# DAQ_IO.net
KiCad netlist of a schematic drawn in Altium Designer
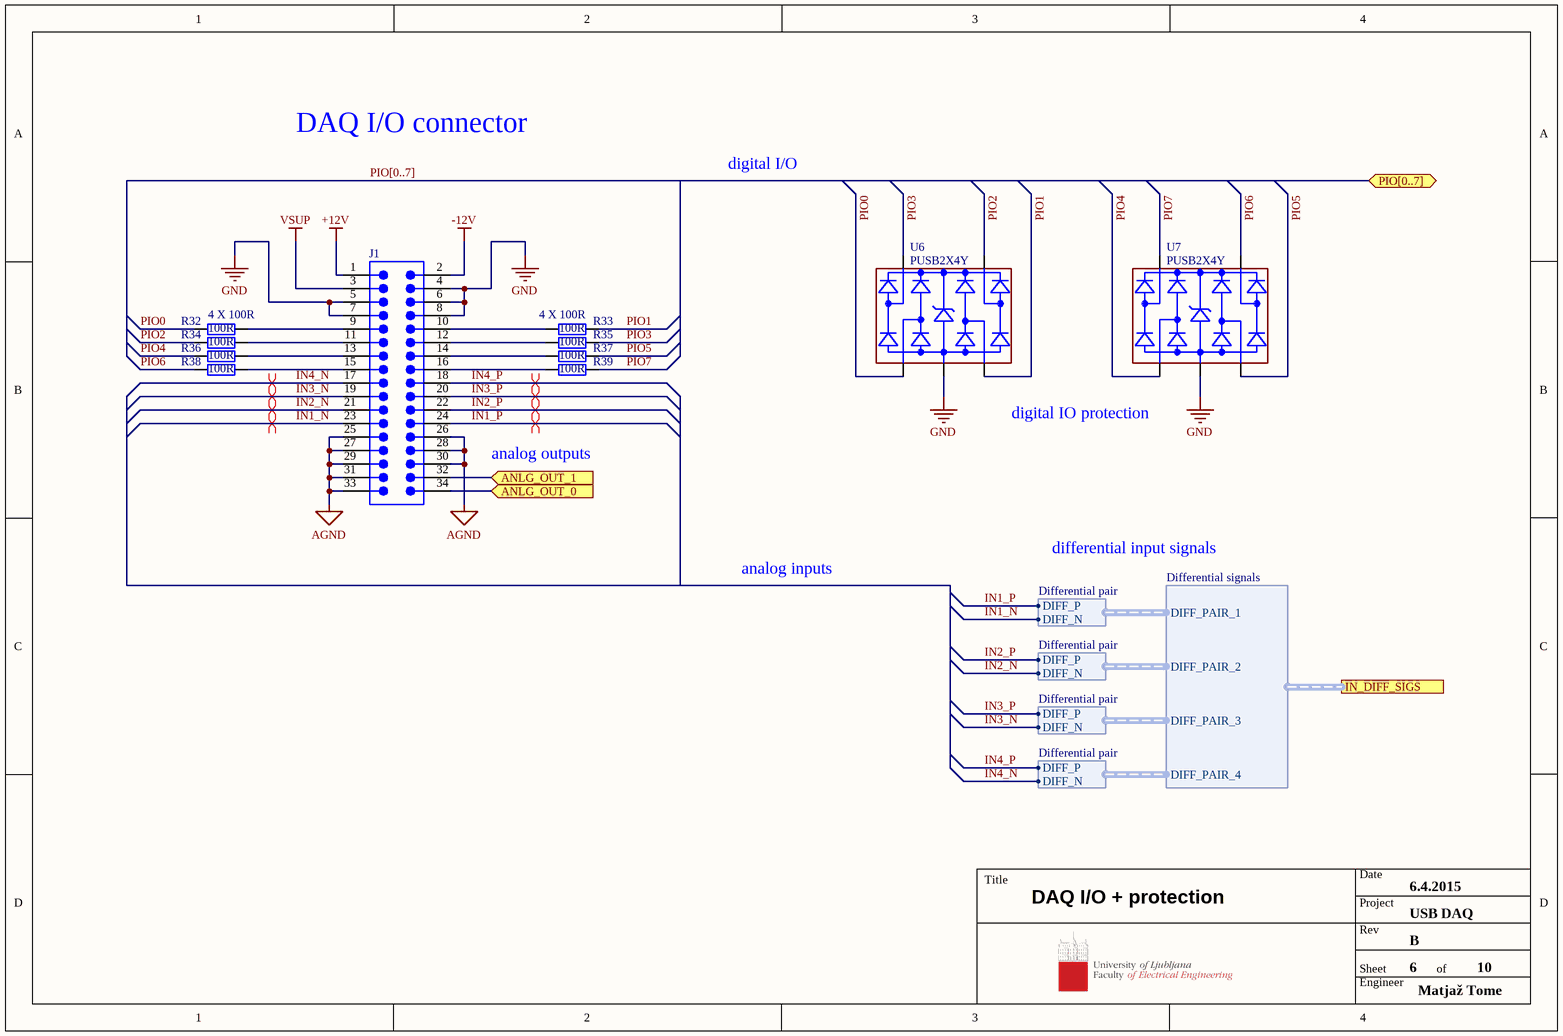
[diagram p0: DAQ_IO.SchDoc]

(export (version "E")
  (design (tool "Eeschema 10.0.6"))
  (components
    (comp (ref "J1")
      (value "2X17")
      (footprint "IDC34R")
      (description "Pin Header, Right Angle, Wire-to-Board, 2.54 mm, 2 Rows, 34 Contacts, Through Hole Right Angle")
      (fields (field (name "MANUFACTURER") "Harting"))
      (libsource (lib "DAQ") (part "09 18 534 7323"))
    )
    (comp (ref "R32")
      (value "100R")
      (footprint "R_0603")
      (description "Generic resistor")
      (fields (field (name "Comment") "comment"))
      (libsource (lib "DAQ") (part "Resistor"))
    )
    (comp (ref "R33")
      (value "100R")
      (footprint "R_0603")
      (description "Generic resistor")
      (fields (field (name "Comment") "comment"))
      (libsource (lib "DAQ") (part "Resistor"))
    )
    (comp (ref "R34")
      (value "100R")
      (footprint "R_0603")
      (description "Generic resistor")
      (fields (field (name "Comment") "comment"))
      (libsource (lib "DAQ") (part "Resistor"))
    )
    (comp (ref "R35")
      (value "100R")
      (footprint "R_0603")
      (description "Generic resistor")
      (fields (field (name "Comment") "comment"))
      (libsource (lib "DAQ") (part "Resistor"))
    )
    (comp (ref "R36")
      (value "100R")
      (footprint "R_0603")
      (description "Generic resistor")
      (fields (field (name "Comment") "comment"))
      (libsource (lib "DAQ") (part "Resistor"))
    )
    (comp (ref "R37")
      (value "100R")
      (footprint "R_0603")
      (description "Generic resistor")
      (fields (field (name "Comment") "comment"))
      (libsource (lib "DAQ") (part "Resistor"))
    )
    (comp (ref "R38")
      (value "100R")
      (footprint "R_0603")
      (description "Generic resistor")
      (fields (field (name "Comment") "comment"))
      (libsource (lib "DAQ") (part "Resistor"))
    )
    (comp (ref "R39")
      (value "100R")
      (footprint "R_0603")
      (description "Generic resistor")
      (fields (field (name "Comment") "comment"))
      (libsource (lib "DAQ") (part "Resistor"))
    )
    (comp (ref "U6")
      (value "PUSB2X4Y")
      (footprint "SOT363")
      (description "ESD protection for high-speed interfaces")
      (fields (field (name "PART NUMBER") "XDE0000") (field (name "MANUFACTURER") "Multicomp"))
      (libsource (lib "DAQ") (part "PUSB2X4Y"))
    )
    (comp (ref "U7")
      (value "PUSB2X4Y")
      (footprint "SOT363")
      (description "ESD protection for high-speed interfaces")
      (fields (field (name "PART NUMBER") "XDE0000") (field (name "MANUFACTURER") "Multicomp"))
      (libsource (lib "DAQ") (part "PUSB2X4Y"))
    )
  )
  (nets
    (net (code "4") (name "+12V") (class "Default")
      (node (ref "J1") (pin "1") (pinfunction "1_1") (pintype "passive"))
    )
    (net (code "5") (name "-12V") (class "Default")
      (node (ref "J1") (pin "2") (pinfunction "2_2") (pintype "passive"))
    )
    (net (code "6") (name "/ANLG_OUT_0") (class "Default")
      (node (ref "J1") (pin "34") (pinfunction "34_34") (pintype "passive"))
    )
    (net (code "7") (name "/ANLG_OUT_1") (class "Default")
      (node (ref "J1") (pin "32") (pinfunction "32_32") (pintype "passive"))
    )
    (net (code "8") (name "/IN1_N") (class "Default")
      (node (ref "J1") (pin "23") (pinfunction "23_23") (pintype "passive"))
    )
    (net (code "9") (name "/IN1_P") (class "Default")
      (node (ref "J1") (pin "24") (pinfunction "24_24") (pintype "passive"))
    )
    (net (code "10") (name "/IN2_N") (class "Default")
      (node (ref "J1") (pin "21") (pinfunction "21_21") (pintype "passive"))
    )
    (net (code "11") (name "/IN2_P") (class "Default")
      (node (ref "J1") (pin "22") (pinfunction "22_22") (pintype "passive"))
    )
    (net (code "12") (name "/IN3_N") (class "Default")
      (node (ref "J1") (pin "19") (pinfunction "19_19") (pintype "passive"))
    )
    (net (code "13") (name "/IN3_P") (class "Default")
      (node (ref "J1") (pin "20") (pinfunction "20_20") (pintype "passive"))
    )
    (net (code "14") (name "/IN4_N") (class "Default")
      (node (ref "J1") (pin "17") (pinfunction "17_17") (pintype "passive"))
    )
    (net (code "15") (name "/IN4_P") (class "Default")
      (node (ref "J1") (pin "18") (pinfunction "18_18") (pintype "passive"))
    )
    (net (code "16") (name "/PIO0") (class "Default")
      (node (ref "R32") (pin "1") (pintype "passive"))
      (node (ref "U6") (pin "1") (pinfunction "1_1") (pintype "passive"))
    )
    (net (code "17") (name "/PIO1") (class "Default")
      (node (ref "R33") (pin "2") (pintype "passive"))
      (node (ref "U6") (pin "3") (pinfunction "3_3") (pintype "passive"))
    )
    (net (code "18") (name "/PIO2") (class "Default")
      (node (ref "R34") (pin "1") (pintype "passive"))
      (node (ref "U6") (pin "4") (pinfunction "4_4") (pintype "passive"))
    )
    (net (code "19") (name "/PIO3") (class "Default")
      (node (ref "R35") (pin "2") (pintype "passive"))
      (node (ref "U6") (pin "6") (pinfunction "6_6") (pintype "passive"))
    )
    (net (code "20") (name "/PIO4") (class "Default")
      (node (ref "R36") (pin "1") (pintype "passive"))
      (node (ref "U7") (pin "1") (pinfunction "1_1") (pintype "passive"))
    )
    (net (code "21") (name "/PIO5") (class "Default")
      (node (ref "R37") (pin "2") (pintype "passive"))
      (node (ref "U7") (pin "3") (pinfunction "3_3") (pintype "passive"))
    )
    (net (code "22") (name "/PIO6") (class "Default")
      (node (ref "R38") (pin "1") (pintype "passive"))
      (node (ref "U7") (pin "4") (pinfunction "4_4") (pintype "passive"))
    )
    (net (code "23") (name "/PIO7") (class "Default")
      (node (ref "R39") (pin "2") (pintype "passive"))
      (node (ref "U7") (pin "6") (pinfunction "6_6") (pintype "passive"))
    )
    (net (code "27") (name "AGND") (class "Default")
      (node (ref "J1") (pin "25") (pinfunction "25_25") (pintype "passive"))
      (node (ref "J1") (pin "26") (pinfunction "26_26") (pintype "passive"))
      (node (ref "J1") (pin "27") (pinfunction "27_27") (pintype "passive"))
      (node (ref "J1") (pin "28") (pinfunction "28_28") (pintype "passive"))
      (node (ref "J1") (pin "29") (pinfunction "29_29") (pintype "passive"))
      (node (ref "J1") (pin "30") (pinfunction "30_30") (pintype "passive"))
      (node (ref "J1") (pin "31") (pinfunction "31_31") (pintype "passive"))
      (node (ref "J1") (pin "33") (pinfunction "33_33") (pintype "passive"))
    )
    (net (code "28") (name "GND") (class "Default")
      (node (ref "J1") (pin "4") (pinfunction "4_4") (pintype "passive"))
      (node (ref "J1") (pin "5") (pinfunction "5_5") (pintype "passive"))
      (node (ref "J1") (pin "6") (pinfunction "6_6") (pintype "passive"))
      (node (ref "J1") (pin "7") (pinfunction "7_7") (pintype "passive"))
      (node (ref "J1") (pin "8") (pinfunction "8_8") (pintype "passive"))
      (node (ref "U6") (pin "2") (pinfunction "2_2") (pintype "passive"))
      (node (ref "U7") (pin "2") (pinfunction "2_2") (pintype "passive"))
    )
    (net (code "29") (name "Net-(J1-Pad9)") (class "Default")
      (node (ref "J1") (pin "9") (pinfunction "9_9") (pintype "passive"))
      (node (ref "R32") (pin "2") (pintype "passive"))
    )
    (net (code "30") (name "Net-(J1-Pad10)") (class "Default")
      (node (ref "J1") (pin "10") (pinfunction "10_10") (pintype "passive"))
      (node (ref "R33") (pin "1") (pintype "passive"))
    )
    (net (code "31") (name "Net-(J1-Pad11)") (class "Default")
      (node (ref "J1") (pin "11") (pinfunction "11_11") (pintype "passive"))
      (node (ref "R34") (pin "2") (pintype "passive"))
    )
    (net (code "32") (name "Net-(J1-Pad12)") (class "Default")
      (node (ref "J1") (pin "12") (pinfunction "12_12") (pintype "passive"))
      (node (ref "R35") (pin "1") (pintype "passive"))
    )
    (net (code "33") (name "Net-(J1-Pad13)") (class "Default")
      (node (ref "J1") (pin "13") (pinfunction "13_13") (pintype "passive"))
      (node (ref "R36") (pin "2") (pintype "passive"))
    )
    (net (code "34") (name "Net-(J1-Pad14)") (class "Default")
      (node (ref "J1") (pin "14") (pinfunction "14_14") (pintype "passive"))
      (node (ref "R37") (pin "1") (pintype "passive"))
    )
    (net (code "35") (name "Net-(J1-Pad15)") (class "Default")
      (node (ref "J1") (pin "15") (pinfunction "15_15") (pintype "passive"))
      (node (ref "R38") (pin "2") (pintype "passive"))
    )
    (net (code "36") (name "Net-(J1-Pad16)") (class "Default")
      (node (ref "J1") (pin "16") (pinfunction "16_16") (pintype "passive"))
      (node (ref "R39") (pin "1") (pintype "passive"))
    )
    (net (code "37") (name "VSUP") (class "Default")
      (node (ref "J1") (pin "3") (pinfunction "3_3") (pintype "passive"))
    )
  )
)
